# ZHSD-ZYNQ-DDR.net
KiCad netlist of a schematic drawn in Altium Designer
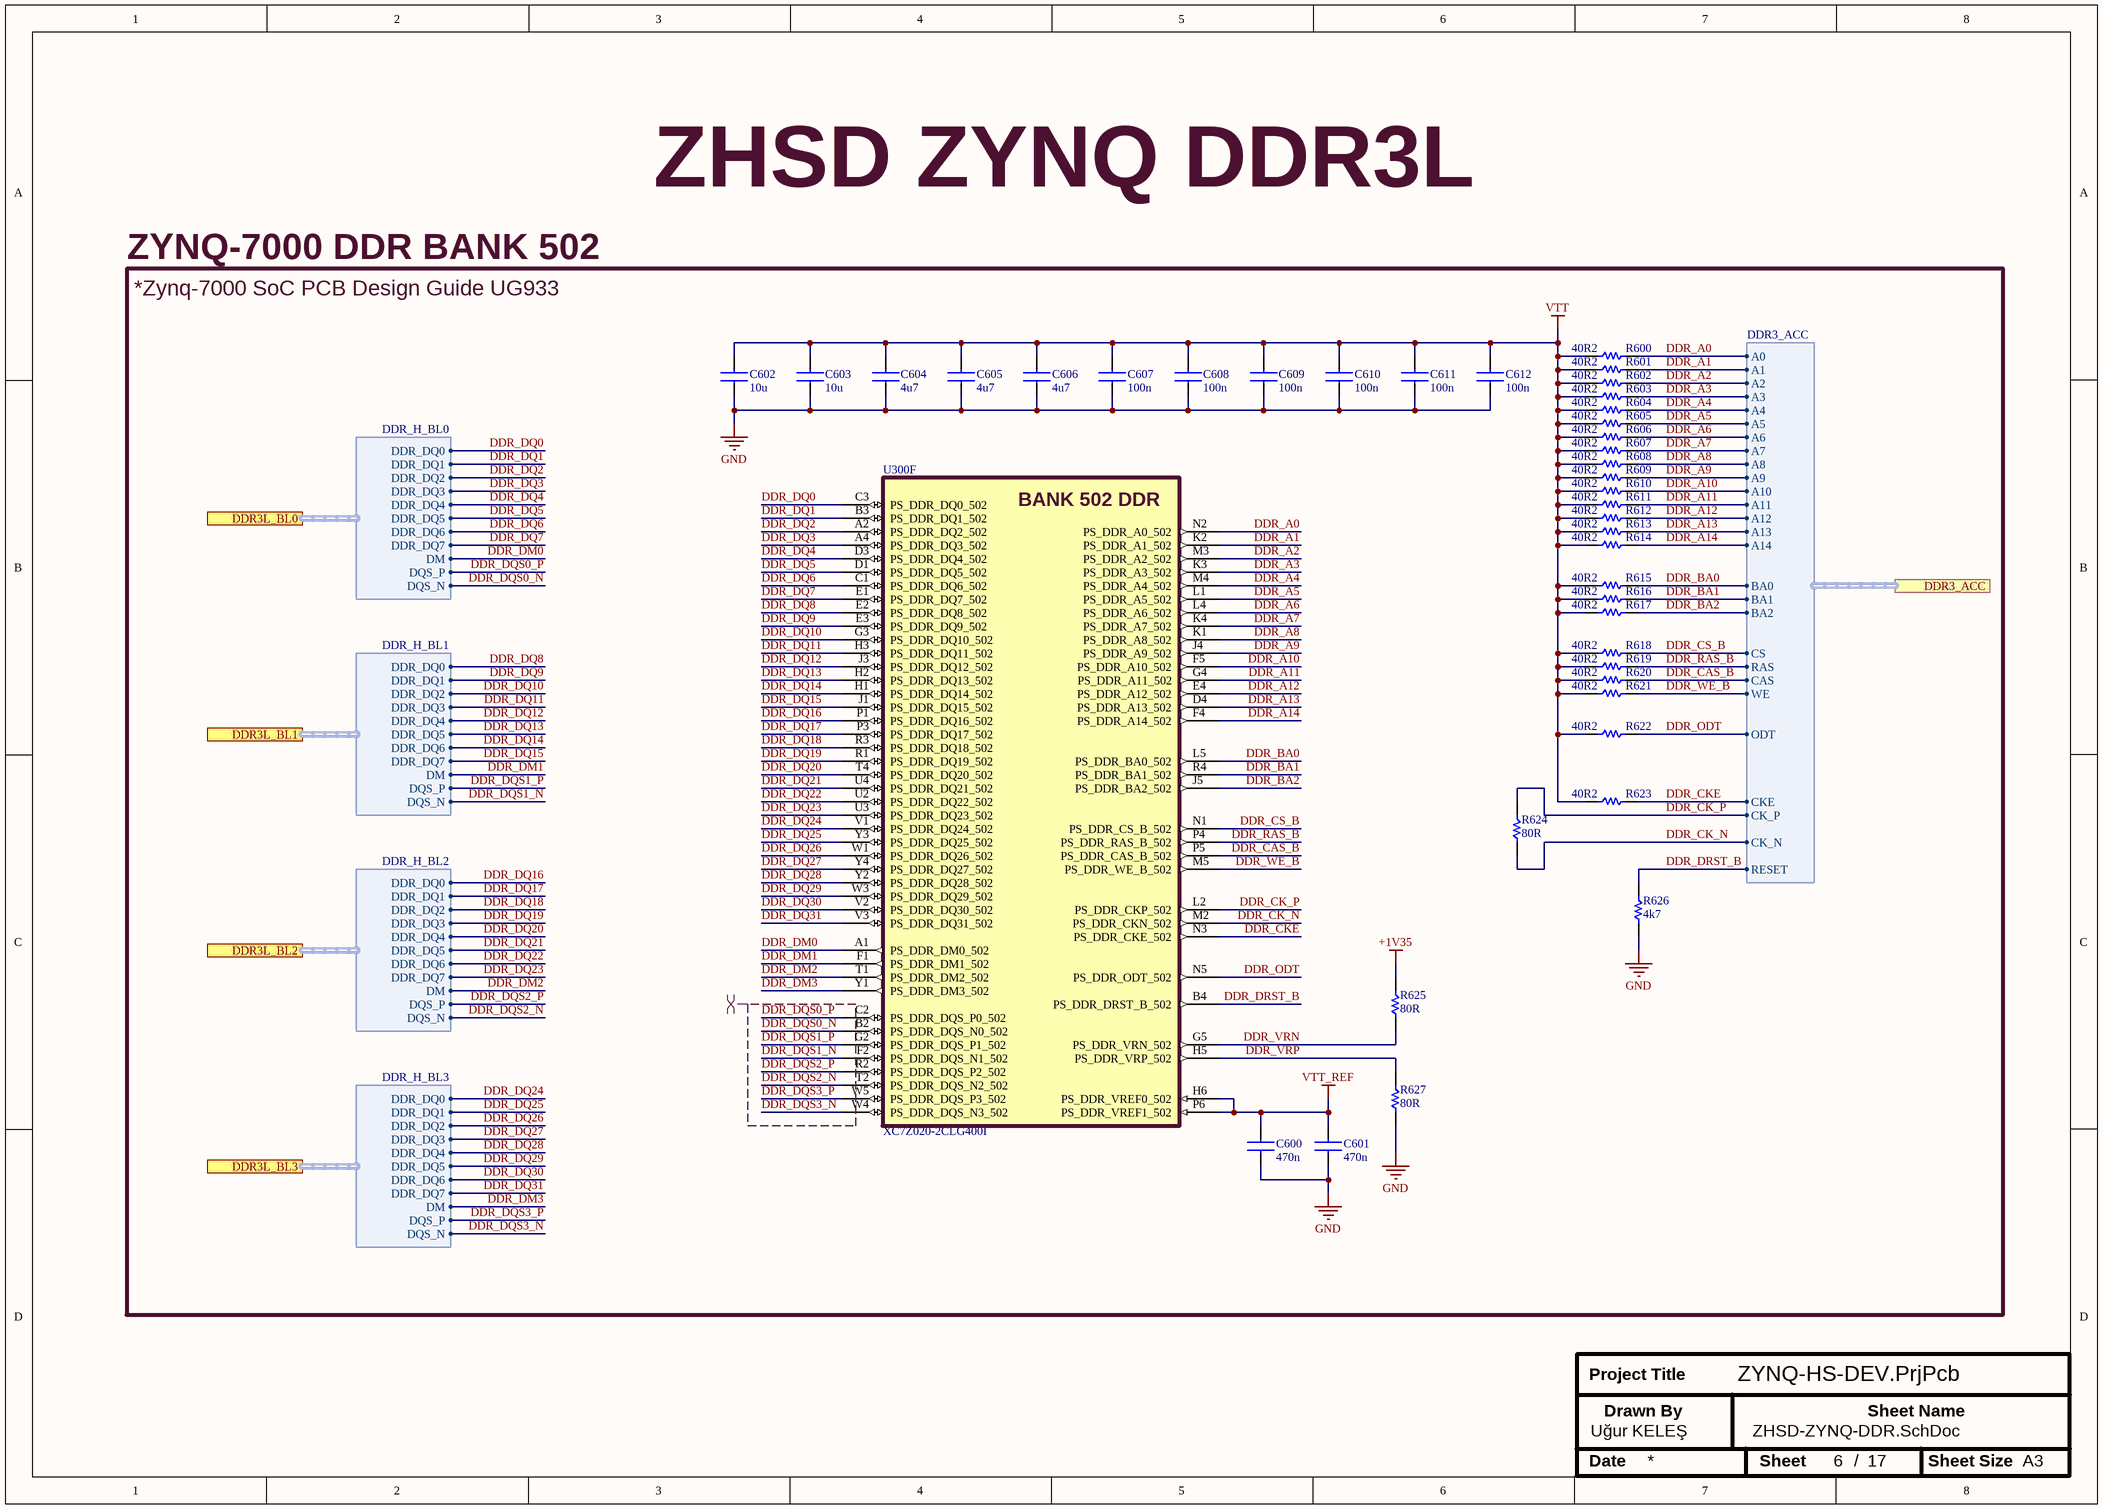
[diagram p0: ZHSD-ZYNQ-DDR.SchDoc]

(export (version "E")
  (design (tool "Eeschema 10.0.6"))
  (components
    (comp (ref "C600")
      (value "470n")
      (footprint "0402CAPC1005X06N")
      (description "CAP CER 0.47UF 6.3V X5R 0402(1005) ±10%")
      (fields (field (name "MANUFACTURER") "Murata Electronics") (field (name "MPN") "GRM155R60J474KE19D"))
      (libsource (lib "UK_Library") (part "GRM155R60J474KE19D"))
    )
    (comp (ref "C601")
      (value "470n")
      (footprint "0402CAPC1005X06N")
      (description "CAP CER 0.47UF 6.3V X5R 0402(1005) ±10%")
      (fields (field (name "MANUFACTURER") "Murata Electronics") (field (name "MPN") "GRM155R60J474KE19D"))
      (libsource (lib "UK_Library") (part "GRM155R60J474KE19D"))
    )
    (comp (ref "C602")
      (value "10u")
      (footprint "0603CAPC1608X09N")
      (description "CAP CER 10UF 10V X7R 0603 (1608) ±20%")
      (fields (field (name "MANUFACTURER") "Murata Electronics") (field (name "MPN") "GRM188Z71A106MA73D"))
      (libsource (lib "UK_Library") (part "GRM188Z71A106MA73D"))
    )
    (comp (ref "C603")
      (value "10u")
      (footprint "0603CAPC1608X09N")
      (description "CAP CER 10UF 10V X7R 0603 (1608) ±20%")
      (fields (field (name "MANUFACTURER") "Murata Electronics") (field (name "MPN") "GRM188Z71A106MA73D"))
      (libsource (lib "UK_Library") (part "GRM188Z71A106MA73D"))
    )
    (comp (ref "C604")
      (value "4u7")
      (footprint "0603CAPC1608X09N")
      (description "CAP CER 4.7UF 10V X5R 0603 (1608) ±10%")
      (fields
        (field (name "MANUFACTURER") "Samsung Electro-Mechanics")
        (field (name "MPN") "CL10A475KP8NNNC")
      )
      (libsource (lib "UK_Library") (part "CL10A475KP8NNNC"))
    )
    (comp (ref "C605")
      (value "4u7")
      (footprint "0603CAPC1608X09N")
      (description "CAP CER 4.7UF 10V X5R 0603 (1608) ±10%")
      (fields
        (field (name "MANUFACTURER") "Samsung Electro-Mechanics")
        (field (name "MPN") "CL10A475KP8NNNC")
      )
      (libsource (lib "UK_Library") (part "CL10A475KP8NNNC"))
    )
    (comp (ref "C606")
      (value "4u7")
      (footprint "0603CAPC1608X09N")
      (description "CAP CER 4.7UF 10V X5R 0603 (1608) ±10%")
      (fields
        (field (name "MANUFACTURER") "Samsung Electro-Mechanics")
        (field (name "MPN") "CL10A475KP8NNNC")
      )
      (libsource (lib "UK_Library") (part "CL10A475KP8NNNC"))
    )
    (comp (ref "C607")
      (value "100n")
      (footprint "0603CAPC1608X09N")
      (description "CAP CER 0.1UF 16V X7R 0402 (1005) ±10%")
      (fields (field (name "MANUFACTURER") "Murata Electronics") (field (name "MPN") "GRM155R71C104KA88J"))
      (libsource (lib "UK_Library") (part "GRM155R71C104KA88J"))
    )
    (comp (ref "C608")
      (value "100n")
      (footprint "0603CAPC1608X09N")
      (description "CAP CER 0.1UF 16V X7R 0402 (1005) ±10%")
      (fields (field (name "MANUFACTURER") "Murata Electronics") (field (name "MPN") "GRM155R71C104KA88J"))
      (libsource (lib "UK_Library") (part "GRM155R71C104KA88J"))
    )
    (comp (ref "C609")
      (value "100n")
      (footprint "0603CAPC1608X09N")
      (description "CAP CER 0.1UF 16V X7R 0402 (1005) ±10%")
      (fields (field (name "MANUFACTURER") "Murata Electronics") (field (name "MPN") "GRM155R71C104KA88J"))
      (libsource (lib "UK_Library") (part "GRM155R71C104KA88J"))
    )
    (comp (ref "C610")
      (value "100n")
      (footprint "0603CAPC1608X09N")
      (description "CAP CER 0.1UF 16V X7R 0402 (1005) ±10%")
      (fields (field (name "MANUFACTURER") "Murata Electronics") (field (name "MPN") "GRM155R71C104KA88J"))
      (libsource (lib "UK_Library") (part "GRM155R71C104KA88J"))
    )
    (comp (ref "C611")
      (value "100n")
      (footprint "0603CAPC1608X09N")
      (description "CAP CER 0.1UF 16V X7R 0402 (1005) ±10%")
      (fields (field (name "MANUFACTURER") "Murata Electronics") (field (name "MPN") "GRM155R71C104KA88J"))
      (libsource (lib "UK_Library") (part "GRM155R71C104KA88J"))
    )
    (comp (ref "C612")
      (value "100n")
      (footprint "0603CAPC1608X09N")
      (description "CAP CER 0.1UF 16V X7R 0402 (1005) ±10%")
      (fields (field (name "MANUFACTURER") "Murata Electronics") (field (name "MPN") "GRM155R71C104KA88J"))
      (libsource (lib "UK_Library") (part "GRM155R71C104KA88J"))
    )
    (comp (ref "R600")
      (value "40R2")
      (footprint "0402RESC1005X04N")
      (description "RES 40.2 OHM 1% 1/16W 0402 (1005)")
      (fields (field (name "MANUFACTURER") "YAGEO") (field (name "MPN") "RC0402FR-0740R2L"))
      (libsource (lib "UK_Library") (part "RC0402FR-0740R2L"))
    )
    (comp (ref "R601")
      (value "40R2")
      (footprint "0402RESC1005X04N")
      (description "RES 40.2 OHM 1% 1/16W 0402 (1005)")
      (fields (field (name "MANUFACTURER") "YAGEO") (field (name "MPN") "RC0402FR-0740R2L"))
      (libsource (lib "UK_Library") (part "RC0402FR-0740R2L"))
    )
    (comp (ref "R602")
      (value "40R2")
      (footprint "0402RESC1005X04N")
      (description "RES 40.2 OHM 1% 1/16W 0402 (1005)")
      (fields (field (name "MANUFACTURER") "YAGEO") (field (name "MPN") "RC0402FR-0740R2L"))
      (libsource (lib "UK_Library") (part "RC0402FR-0740R2L"))
    )
    (comp (ref "R603")
      (value "40R2")
      (footprint "0402RESC1005X04N")
      (description "RES 40.2 OHM 1% 1/16W 0402 (1005)")
      (fields (field (name "MANUFACTURER") "YAGEO") (field (name "MPN") "RC0402FR-0740R2L"))
      (libsource (lib "UK_Library") (part "RC0402FR-0740R2L"))
    )
    (comp (ref "R604")
      (value "40R2")
      (footprint "0402RESC1005X04N")
      (description "RES 40.2 OHM 1% 1/16W 0402 (1005)")
      (fields (field (name "MANUFACTURER") "YAGEO") (field (name "MPN") "RC0402FR-0740R2L"))
      (libsource (lib "UK_Library") (part "RC0402FR-0740R2L"))
    )
    (comp (ref "R605")
      (value "40R2")
      (footprint "0402RESC1005X04N")
      (description "RES 40.2 OHM 1% 1/16W 0402 (1005)")
      (fields (field (name "MANUFACTURER") "YAGEO") (field (name "MPN") "RC0402FR-0740R2L"))
      (libsource (lib "UK_Library") (part "RC0402FR-0740R2L"))
    )
    (comp (ref "R606")
      (value "40R2")
      (footprint "0402RESC1005X04N")
      (description "RES 40.2 OHM 1% 1/16W 0402 (1005)")
      (fields (field (name "MANUFACTURER") "YAGEO") (field (name "MPN") "RC0402FR-0740R2L"))
      (libsource (lib "UK_Library") (part "RC0402FR-0740R2L"))
    )
    (comp (ref "R607")
      (value "40R2")
      (footprint "0402RESC1005X04N")
      (description "RES 40.2 OHM 1% 1/16W 0402 (1005)")
      (fields (field (name "MANUFACTURER") "YAGEO") (field (name "MPN") "RC0402FR-0740R2L"))
      (libsource (lib "UK_Library") (part "RC0402FR-0740R2L"))
    )
    (comp (ref "R608")
      (value "40R2")
      (footprint "0402RESC1005X04N")
      (description "RES 40.2 OHM 1% 1/16W 0402 (1005)")
      (fields (field (name "MANUFACTURER") "YAGEO") (field (name "MPN") "RC0402FR-0740R2L"))
      (libsource (lib "UK_Library") (part "RC0402FR-0740R2L"))
    )
    (comp (ref "R609")
      (value "40R2")
      (footprint "0402RESC1005X04N")
      (description "RES 40.2 OHM 1% 1/16W 0402 (1005)")
      (fields (field (name "MANUFACTURER") "YAGEO") (field (name "MPN") "RC0402FR-0740R2L"))
      (libsource (lib "UK_Library") (part "RC0402FR-0740R2L"))
    )
    (comp (ref "R610")
      (value "40R2")
      (footprint "0402RESC1005X04N")
      (description "RES 40.2 OHM 1% 1/16W 0402 (1005)")
      (fields (field (name "MANUFACTURER") "YAGEO") (field (name "MPN") "RC0402FR-0740R2L"))
      (libsource (lib "UK_Library") (part "RC0402FR-0740R2L"))
    )
    (comp (ref "R611")
      (value "40R2")
      (footprint "0402RESC1005X04N")
      (description "RES 40.2 OHM 1% 1/16W 0402 (1005)")
      (fields (field (name "MANUFACTURER") "YAGEO") (field (name "MPN") "RC0402FR-0740R2L"))
      (libsource (lib "UK_Library") (part "RC0402FR-0740R2L"))
    )
    (comp (ref "R612")
      (value "40R2")
      (footprint "0402RESC1005X04N")
      (description "RES 40.2 OHM 1% 1/16W 0402 (1005)")
      (fields (field (name "MANUFACTURER") "YAGEO") (field (name "MPN") "RC0402FR-0740R2L"))
      (libsource (lib "UK_Library") (part "RC0402FR-0740R2L"))
    )
    (comp (ref "R613")
      (value "40R2")
      (footprint "0402RESC1005X04N")
      (description "RES 40.2 OHM 1% 1/16W 0402 (1005)")
      (fields (field (name "MANUFACTURER") "YAGEO") (field (name "MPN") "RC0402FR-0740R2L"))
      (libsource (lib "UK_Library") (part "RC0402FR-0740R2L"))
    )
    (comp (ref "R614")
      (value "40R2")
      (footprint "0402RESC1005X04N")
      (description "RES 40.2 OHM 1% 1/16W 0402 (1005)")
      (fields (field (name "MANUFACTURER") "YAGEO") (field (name "MPN") "RC0402FR-0740R2L"))
      (libsource (lib "UK_Library") (part "RC0402FR-0740R2L"))
    )
    (comp (ref "R615")
      (value "40R2")
      (footprint "0402RESC1005X04N")
      (description "RES 40.2 OHM 1% 1/16W 0402 (1005)")
      (fields (field (name "MANUFACTURER") "YAGEO") (field (name "MPN") "RC0402FR-0740R2L"))
      (libsource (lib "UK_Library") (part "RC0402FR-0740R2L"))
    )
    (comp (ref "R616")
      (value "40R2")
      (footprint "0402RESC1005X04N")
      (description "RES 40.2 OHM 1% 1/16W 0402 (1005)")
      (fields (field (name "MANUFACTURER") "YAGEO") (field (name "MPN") "RC0402FR-0740R2L"))
      (libsource (lib "UK_Library") (part "RC0402FR-0740R2L"))
    )
    (comp (ref "R617")
      (value "40R2")
      (footprint "0402RESC1005X04N")
      (description "RES 40.2 OHM 1% 1/16W 0402 (1005)")
      (fields (field (name "MANUFACTURER") "YAGEO") (field (name "MPN") "RC0402FR-0740R2L"))
      (libsource (lib "UK_Library") (part "RC0402FR-0740R2L"))
    )
    (comp (ref "R618")
      (value "40R2")
      (footprint "0402RESC1005X04N")
      (description "RES 40.2 OHM 1% 1/16W 0402 (1005)")
      (fields (field (name "MANUFACTURER") "YAGEO") (field (name "MPN") "RC0402FR-0740R2L"))
      (libsource (lib "UK_Library") (part "RC0402FR-0740R2L"))
    )
    (comp (ref "R619")
      (value "40R2")
      (footprint "0402RESC1005X04N")
      (description "RES 40.2 OHM 1% 1/16W 0402 (1005)")
      (fields (field (name "MANUFACTURER") "YAGEO") (field (name "MPN") "RC0402FR-0740R2L"))
      (libsource (lib "UK_Library") (part "RC0402FR-0740R2L"))
    )
    (comp (ref "R620")
      (value "40R2")
      (footprint "0402RESC1005X04N")
      (description "RES 40.2 OHM 1% 1/16W 0402 (1005)")
      (fields (field (name "MANUFACTURER") "YAGEO") (field (name "MPN") "RC0402FR-0740R2L"))
      (libsource (lib "UK_Library") (part "RC0402FR-0740R2L"))
    )
    (comp (ref "R621")
      (value "40R2")
      (footprint "0402RESC1005X04N")
      (description "RES 40.2 OHM 1% 1/16W 0402 (1005)")
      (fields (field (name "MANUFACTURER") "YAGEO") (field (name "MPN") "RC0402FR-0740R2L"))
      (libsource (lib "UK_Library") (part "RC0402FR-0740R2L"))
    )
    (comp (ref "R622")
      (value "40R2")
      (footprint "0402RESC1005X04N")
      (description "RES 40.2 OHM 1% 1/16W 0402 (1005)")
      (fields (field (name "MANUFACTURER") "YAGEO") (field (name "MPN") "RC0402FR-0740R2L"))
      (libsource (lib "UK_Library") (part "RC0402FR-0740R2L"))
    )
    (comp (ref "R623")
      (value "40R2")
      (footprint "0402RESC1005X04N")
      (description "RES 40.2 OHM 1% 1/16W 0402 (1005)")
      (fields (field (name "MANUFACTURER") "YAGEO") (field (name "MPN") "RC0402FR-0740R2L"))
      (libsource (lib "UK_Library") (part "RC0402FR-0740R2L"))
    )
    (comp (ref "R624")
      (value "80R")
      (footprint "0402RESC1005X04N")
      (description "RES 80 OHM 1% 1/16W 0402 (1005)")
      (fields (field (name "MANUFACTURER") "YAGEO") (field (name "MPN") "RT0402FRE0780RL"))
      (libsource (lib "UK_Library") (part "RT0402FRE0780RL"))
    )
    (comp (ref "R625")
      (value "80R")
      (footprint "0402RESC1005X04N")
      (description "RES 80 OHM 1% 1/16W 0402 (1005)")
      (fields (field (name "MANUFACTURER") "YAGEO") (field (name "MPN") "RT0402FRE0780RL"))
      (libsource (lib "UK_Library") (part "RT0402FRE0780RL"))
    )
    (comp (ref "R626")
      (value "4k7")
      (footprint "0402RESC1005X04N")
      (description "RES 4.7K OHM 5% 1/16W 0402 (1005)")
      (fields (field (name "MANUFACTURER") "YAGEO") (field (name "MPN") "RT0402FRE0780RL"))
      (libsource (lib "UK_Library") (part "RC0402JR-074K7L"))
    )
    (comp (ref "R627")
      (value "80R")
      (footprint "0402RESC1005X04N")
      (description "RES 80 OHM 1% 1/16W 0402 (1005)")
      (fields (field (name "MANUFACTURER") "YAGEO") (field (name "MPN") "RT0402FRE0780RL"))
      (libsource (lib "UK_Library") (part "RT0402FRE0780RL"))
    )
    (comp (ref "U300")
      (value "XC7Z020-2CLG400I")
      (footprint "BGA400C80P20X20_1700X1700X147")
      (fields (field (name "MANUFACTURER") "AMD/XILINX"))
      (libsource (lib "UK_Library") (part "XC7Z020-2CLG400I"))
    )
  )
  (nets
    (net (code "6") (name "+1V35") (class "Default")
      (node (ref "R625") (pin "2") (pinfunction "2_2") (pintype "passive"))
    )
    (net (code "7") (name "/DDR_A0") (class "Default")
      (node (ref "R600") (pin "2") (pinfunction "2_2") (pintype "passive"))
      (node (ref "U300") (pin "N2") (pinfunction "PS_DDR_A0_502_N2") (pintype "output"))
    )
    (net (code "8") (name "/DDR_A1") (class "Default")
      (node (ref "R601") (pin "2") (pinfunction "2_2") (pintype "passive"))
      (node (ref "U300") (pin "K2") (pinfunction "PS_DDR_A1_502_K2") (pintype "output"))
    )
    (net (code "9") (name "/DDR_A2") (class "Default")
      (node (ref "R602") (pin "2") (pinfunction "2_2") (pintype "passive"))
      (node (ref "U300") (pin "M3") (pinfunction "PS_DDR_A2_502_M3") (pintype "output"))
    )
    (net (code "10") (name "/DDR_A3") (class "Default")
      (node (ref "R603") (pin "2") (pinfunction "2_2") (pintype "passive"))
      (node (ref "U300") (pin "K3") (pinfunction "PS_DDR_A3_502_K3") (pintype "output"))
    )
    (net (code "11") (name "/DDR_A4") (class "Default")
      (node (ref "R604") (pin "2") (pinfunction "2_2") (pintype "passive"))
      (node (ref "U300") (pin "M4") (pinfunction "PS_DDR_A4_502_M4") (pintype "output"))
    )
    (net (code "12") (name "/DDR_A5") (class "Default")
      (node (ref "R605") (pin "2") (pinfunction "2_2") (pintype "passive"))
      (node (ref "U300") (pin "L1") (pinfunction "PS_DDR_A5_502_L1") (pintype "output"))
    )
    (net (code "13") (name "/DDR_A6") (class "Default")
      (node (ref "R606") (pin "2") (pinfunction "2_2") (pintype "passive"))
      (node (ref "U300") (pin "L4") (pinfunction "PS_DDR_A6_502_L4") (pintype "output"))
    )
    (net (code "14") (name "/DDR_A7") (class "Default")
      (node (ref "R607") (pin "2") (pinfunction "2_2") (pintype "passive"))
      (node (ref "U300") (pin "K4") (pinfunction "PS_DDR_A7_502_K4") (pintype "output"))
    )
    (net (code "15") (name "/DDR_A8") (class "Default")
      (node (ref "R608") (pin "2") (pinfunction "2_2") (pintype "passive"))
      (node (ref "U300") (pin "K1") (pinfunction "PS_DDR_A8_502_K1") (pintype "output"))
    )
    (net (code "16") (name "/DDR_A9") (class "Default")
      (node (ref "R609") (pin "2") (pinfunction "2_2") (pintype "passive"))
      (node (ref "U300") (pin "J4") (pinfunction "PS_DDR_A9_502_J4") (pintype "output"))
    )
    (net (code "17") (name "/DDR_A10") (class "Default")
      (node (ref "R610") (pin "2") (pinfunction "2_2") (pintype "passive"))
      (node (ref "U300") (pin "F5") (pinfunction "PS_DDR_A10_502_F5") (pintype "output"))
    )
    (net (code "18") (name "/DDR_A11") (class "Default")
      (node (ref "R611") (pin "2") (pinfunction "2_2") (pintype "passive"))
      (node (ref "U300") (pin "G4") (pinfunction "PS_DDR_A11_502_G4") (pintype "output"))
    )
    (net (code "19") (name "/DDR_A12") (class "Default")
      (node (ref "R612") (pin "2") (pinfunction "2_2") (pintype "passive"))
      (node (ref "U300") (pin "E4") (pinfunction "PS_DDR_A12_502_E4") (pintype "output"))
    )
    (net (code "20") (name "/DDR_A13") (class "Default")
      (node (ref "R613") (pin "2") (pinfunction "2_2") (pintype "passive"))
      (node (ref "U300") (pin "D4") (pinfunction "PS_DDR_A13_502_D4") (pintype "output"))
    )
    (net (code "21") (name "/DDR_A14") (class "Default")
      (node (ref "R614") (pin "2") (pinfunction "2_2") (pintype "passive"))
      (node (ref "U300") (pin "F4") (pinfunction "PS_DDR_A14_502_F4") (pintype "output"))
    )
    (net (code "22") (name "/DDR_BA0") (class "Default")
      (node (ref "R615") (pin "2") (pinfunction "2_2") (pintype "passive"))
      (node (ref "U300") (pin "L5") (pinfunction "PS_DDR_BA0_502_L5") (pintype "output"))
    )
    (net (code "23") (name "/DDR_BA1") (class "Default")
      (node (ref "R616") (pin "2") (pinfunction "2_2") (pintype "passive"))
      (node (ref "U300") (pin "R4") (pinfunction "PS_DDR_BA1_502_R4") (pintype "output"))
    )
    (net (code "24") (name "/DDR_BA2") (class "Default")
      (node (ref "R617") (pin "2") (pinfunction "2_2") (pintype "passive"))
      (node (ref "U300") (pin "J5") (pinfunction "PS_DDR_BA2_502_J5") (pintype "output"))
    )
    (net (code "25") (name "/DDR_CAS_B") (class "Default")
      (node (ref "R620") (pin "2") (pinfunction "2_2") (pintype "passive"))
      (node (ref "U300") (pin "P5") (pinfunction "PS_DDR_CAS_B_502_P5") (pintype "output"))
    )
    (net (code "26") (name "/DDR_CKE") (class "Default")
      (node (ref "R623") (pin "2") (pinfunction "2_2") (pintype "passive"))
      (node (ref "U300") (pin "N3") (pinfunction "PS_DDR_CKE_502_N3") (pintype "output"))
    )
    (net (code "27") (name "/DDR_CK_N") (class "Default")
      (node (ref "R624") (pin "1") (pinfunction "1_1") (pintype "passive"))
      (node (ref "U300") (pin "M2") (pinfunction "PS_DDR_CKN_502_M2") (pintype "output"))
    )
    (net (code "28") (name "/DDR_CK_P") (class "Default")
      (node (ref "R624") (pin "2") (pinfunction "2_2") (pintype "passive"))
      (node (ref "U300") (pin "L2") (pinfunction "PS_DDR_CKP_502_L2") (pintype "output"))
    )
    (net (code "29") (name "/DDR_CS_B") (class "Default")
      (node (ref "R618") (pin "2") (pinfunction "2_2") (pintype "passive"))
      (node (ref "U300") (pin "N1") (pinfunction "PS_DDR_CS_B_502_N1") (pintype "output"))
    )
    (net (code "30") (name "/DDR_DM0") (class "Default")
      (node (ref "U300") (pin "A1") (pinfunction "PS_DDR_DM0_502_A1") (pintype "output"))
    )
    (net (code "31") (name "/DDR_DM1") (class "Default")
      (node (ref "U300") (pin "F1") (pinfunction "PS_DDR_DM1_502_F1") (pintype "output"))
    )
    (net (code "32") (name "/DDR_DM2") (class "Default")
      (node (ref "U300") (pin "T1") (pinfunction "PS_DDR_DM2_502_T1") (pintype "output"))
    )
    (net (code "33") (name "/DDR_DM3") (class "Default")
      (node (ref "U300") (pin "Y1") (pinfunction "PS_DDR_DM3_502_Y1") (pintype "output"))
    )
    (net (code "34") (name "/DDR_DQ0") (class "Default")
      (node (ref "U300") (pin "C3") (pinfunction "PS_DDR_DQ0_502_C3") (pintype "bidirectional"))
    )
    (net (code "35") (name "/DDR_DQ1") (class "Default")
      (node (ref "U300") (pin "B3") (pinfunction "PS_DDR_DQ1_502_B3") (pintype "bidirectional"))
    )
    (net (code "36") (name "/DDR_DQ2") (class "Default")
      (node (ref "U300") (pin "A2") (pinfunction "PS_DDR_DQ2_502_A2") (pintype "bidirectional"))
    )
    (net (code "37") (name "/DDR_DQ3") (class "Default")
      (node (ref "U300") (pin "A4") (pinfunction "PS_DDR_DQ3_502_A4") (pintype "bidirectional"))
    )
    (net (code "38") (name "/DDR_DQ4") (class "Default")
      (node (ref "U300") (pin "D3") (pinfunction "PS_DDR_DQ4_502_D3") (pintype "bidirectional"))
    )
    (net (code "39") (name "/DDR_DQ5") (class "Default")
      (node (ref "U300") (pin "D1") (pinfunction "PS_DDR_DQ5_502_D1") (pintype "bidirectional"))
    )
    (net (code "40") (name "/DDR_DQ6") (class "Default")
      (node (ref "U300") (pin "C1") (pinfunction "PS_DDR_DQ6_502_C1") (pintype "bidirectional"))
    )
    (net (code "41") (name "/DDR_DQ7") (class "Default")
      (node (ref "U300") (pin "E1") (pinfunction "PS_DDR_DQ7_502_E1") (pintype "bidirectional"))
    )
    (net (code "42") (name "/DDR_DQ8") (class "Default")
      (node (ref "U300") (pin "E2") (pinfunction "PS_DDR_DQ8_502_E2") (pintype "bidirectional"))
    )
    (net (code "43") (name "/DDR_DQ9") (class "Default")
      (node (ref "U300") (pin "E3") (pinfunction "PS_DDR_DQ9_502_E3") (pintype "bidirectional"))
    )
    (net (code "44") (name "/DDR_DQ10") (class "Default")
      (node (ref "U300") (pin "G3") (pinfunction "PS_DDR_DQ10_502_G3") (pintype "bidirectional"))
    )
    (net (code "45") (name "/DDR_DQ11") (class "Default")
      (node (ref "U300") (pin "H3") (pinfunction "PS_DDR_DQ11_502_H3") (pintype "bidirectional"))
    )
    (net (code "46") (name "/DDR_DQ12") (class "Default")
      (node (ref "U300") (pin "J3") (pinfunction "PS_DDR_DQ12_502_J3") (pintype "bidirectional"))
    )
    (net (code "47") (name "/DDR_DQ13") (class "Default")
      (node (ref "U300") (pin "H2") (pinfunction "PS_DDR_DQ13_502_H2") (pintype "bidirectional"))
    )
    (net (code "48") (name "/DDR_DQ14") (class "Default")
      (node (ref "U300") (pin "H1") (pinfunction "PS_DDR_DQ14_502_H1") (pintype "bidirectional"))
    )
    (net (code "49") (name "/DDR_DQ15") (class "Default")
      (node (ref "U300") (pin "J1") (pinfunction "PS_DDR_DQ15_502_J1") (pintype "bidirectional"))
    )
    (net (code "50") (name "/DDR_DQ16") (class "Default")
      (node (ref "U300") (pin "P1") (pinfunction "PS_DDR_DQ16_502_P1") (pintype "bidirectional"))
    )
    (net (code "51") (name "/DDR_DQ17") (class "Default")
      (node (ref "U300") (pin "P3") (pinfunction "PS_DDR_DQ17_502_P3") (pintype "bidirectional"))
    )
    (net (code "52") (name "/DDR_DQ18") (class "Default")
      (node (ref "U300") (pin "R3") (pinfunction "PS_DDR_DQ18_502_R3") (pintype "bidirectional"))
    )
    (net (code "53") (name "/DDR_DQ19") (class "Default")
      (node (ref "U300") (pin "R1") (pinfunction "PS_DDR_DQ19_502_R1") (pintype "bidirectional"))
    )
    (net (code "54") (name "/DDR_DQ20") (class "Default")
      (node (ref "U300") (pin "T4") (pinfunction "PS_DDR_DQ20_502_T4") (pintype "bidirectional"))
    )
    (net (code "55") (name "/DDR_DQ21") (class "Default")
      (node (ref "U300") (pin "U4") (pinfunction "PS_DDR_DQ21_502_U4") (pintype "bidirectional"))
    )
    (net (code "56") (name "/DDR_DQ22") (class "Default")
      (node (ref "U300") (pin "U2") (pinfunction "PS_DDR_DQ22_502_U2") (pintype "bidirectional"))
    )
    (net (code "57") (name "/DDR_DQ23") (class "Default")
      (node (ref "U300") (pin "U3") (pinfunction "PS_DDR_DQ23_502_U3") (pintype "bidirectional"))
    )
    (net (code "58") (name "/DDR_DQ24") (class "Default")
      (node (ref "U300") (pin "V1") (pinfunction "PS_DDR_DQ24_502_V1") (pintype "bidirectional"))
    )
    (net (code "59") (name "/DDR_DQ25") (class "Default")
      (node (ref "U300") (pin "Y3") (pinfunction "PS_DDR_DQ25_502_Y3") (pintype "bidirectional"))
    )
    (net (code "60") (name "/DDR_DQ26") (class "Default")
      (node (ref "U300") (pin "W1") (pinfunction "PS_DDR_DQ26_502_W1") (pintype "bidirectional"))
    )
    (net (code "61") (name "/DDR_DQ27") (class "Default")
      (node (ref "U300") (pin "Y4") (pinfunction "PS_DDR_DQ27_502_Y4") (pintype "bidirectional"))
    )
    (net (code "62") (name "/DDR_DQ28") (class "Default")
      (node (ref "U300") (pin "Y2") (pinfunction "PS_DDR_DQ28_502_Y2") (pintype "bidirectional"))
    )
    (net (code "63") (name "/DDR_DQ29") (class "Default")
      (node (ref "U300") (pin "W3") (pinfunction "PS_DDR_DQ29_502_W3") (pintype "bidirectional"))
    )
    (net (code "64") (name "/DDR_DQ30") (class "Default")
      (node (ref "U300") (pin "V2") (pinfunction "PS_DDR_DQ30_502_V2") (pintype "bidirectional"))
    )
    (net (code "65") (name "/DDR_DQ31") (class "Default")
      (node (ref "U300") (pin "V3") (pinfunction "PS_DDR_DQ31_502_V3") (pintype "bidirectional"))
    )
    (net (code "66") (name "/DDR_DQS0_N") (class "Default")
      (node (ref "U300") (pin "B2") (pinfunction "PS_DDR_DQS_N0_502_B2") (pintype "bidirectional"))
    )
    (net (code "67") (name "/DDR_DQS0_P") (class "Default")
      (node (ref "U300") (pin "C2") (pinfunction "PS_DDR_DQS_P0_502_C2") (pintype "bidirectional"))
    )
    (net (code "68") (name "/DDR_DQS1_N") (class "Default")
      (node (ref "U300") (pin "F2") (pinfunction "PS_DDR_DQS_N1_502_F2") (pintype "bidirectional"))
    )
    (net (code "69") (name "/DDR_DQS1_P") (class "Default")
      (node (ref "U300") (pin "G2") (pinfunction "PS_DDR_DQS_P1_502_G2") (pintype "bidirectional"))
    )
    (net (code "70") (name "/DDR_DQS2_N") (class "Default")
      (node (ref "U300") (pin "T2") (pinfunction "PS_DDR_DQS_N2_502_T2") (pintype "bidirectional"))
    )
    (net (code "71") (name "/DDR_DQS2_P") (class "Default")
      (node (ref "U300") (pin "R2") (pinfunction "PS_DDR_DQS_P2_502_R2") (pintype "bidirectional"))
    )
    (net (code "72") (name "/DDR_DQS3_N") (class "Default")
      (node (ref "U300") (pin "W4") (pinfunction "PS_DDR_DQS_N3_502_W4") (pintype "bidirectional"))
    )
    (net (code "73") (name "/DDR_DQS3_P") (class "Default")
      (node (ref "U300") (pin "W5") (pinfunction "PS_DDR_DQS_P3_502_W5") (pintype "bidirectional"))
    )
    (net (code "74") (name "/DDR_DRST_B") (class "Default")
      (node (ref "R626") (pin "2") (pinfunction "2_2") (pintype "passive"))
      (node (ref "U300") (pin "B4") (pinfunction "PS_DDR_DRST_B_502_B4") (pintype "output"))
    )
    (net (code "75") (name "/DDR_ODT") (class "Default")
      (node (ref "R622") (pin "2") (pinfunction "2_2") (pintype "passive"))
      (node (ref "U300") (pin "N5") (pinfunction "PS_DDR_ODT_502_N5") (pintype "output"))
    )
    (net (code "76") (name "/DDR_RAS_B") (class "Default")
      (node (ref "R619") (pin "2") (pinfunction "2_2") (pintype "passive"))
      (node (ref "U300") (pin "P4") (pinfunction "PS_DDR_RAS_B_502_P4") (pintype "output"))
    )
    (net (code "77") (name "/DDR_VRN") (class "Default")
      (node (ref "R625") (pin "1") (pinfunction "1_1") (pintype "passive"))
      (node (ref "U300") (pin "G5") (pinfunction "PS_DDR_VRN_502_G5") (pintype "output"))
    )
    (net (code "78") (name "/DDR_VRP") (class "Default")
      (node (ref "R627") (pin "2") (pinfunction "2_2") (pintype "passive"))
      (node (ref "U300") (pin "H5") (pinfunction "PS_DDR_VRP_502_H5") (pintype "output"))
    )
    (net (code "79") (name "/DDR_WE_B") (class "Default")
      (node (ref "R621") (pin "2") (pinfunction "2_2") (pintype "passive"))
      (node (ref "U300") (pin "M5") (pinfunction "PS_DDR_WE_B_502_M5") (pintype "output"))
    )
    (net (code "85") (name "GND") (class "Default")
      (node (ref "C600") (pin "1") (pinfunction "1_1") (pintype "passive"))
      (node (ref "C601") (pin "1") (pinfunction "1_1") (pintype "passive"))
      (node (ref "C602") (pin "1") (pinfunction "1_1") (pintype "passive"))
      (node (ref "C603") (pin "1") (pinfunction "1_1") (pintype "passive"))
      (node (ref "C604") (pin "1") (pinfunction "1_1") (pintype "passive"))
      (node (ref "C605") (pin "1") (pinfunction "1_1") (pintype "passive"))
      (node (ref "C606") (pin "1") (pinfunction "1_1") (pintype "passive"))
      (node (ref "C607") (pin "1") (pinfunction "1_1") (pintype "passive"))
      (node (ref "C608") (pin "1") (pinfunction "1_1") (pintype "passive"))
      (node (ref "C609") (pin "1") (pinfunction "1_1") (pintype "passive"))
      (node (ref "C610") (pin "1") (pinfunction "1_1") (pintype "passive"))
      (node (ref "C611") (pin "1") (pinfunction "1_1") (pintype "passive"))
      (node (ref "C612") (pin "1") (pinfunction "1_1") (pintype "passive"))
      (node (ref "R626") (pin "1") (pinfunction "1_1") (pintype "passive"))
      (node (ref "R627") (pin "1") (pinfunction "1_1") (pintype "passive"))
    )
    (net (code "86") (name "VTT") (class "Default")
      (node (ref "C602") (pin "2") (pinfunction "2_2") (pintype "passive"))
      (node (ref "C603") (pin "2") (pinfunction "2_2") (pintype "passive"))
      (node (ref "C604") (pin "2") (pinfunction "2_2") (pintype "passive"))
      (node (ref "C605") (pin "2") (pinfunction "2_2") (pintype "passive"))
      (node (ref "C606") (pin "2") (pinfunction "2_2") (pintype "passive"))
      (node (ref "C607") (pin "2") (pinfunction "2_2") (pintype "passive"))
      (node (ref "C608") (pin "2") (pinfunction "2_2") (pintype "passive"))
      (node (ref "C609") (pin "2") (pinfunction "2_2") (pintype "passive"))
      (node (ref "C610") (pin "2") (pinfunction "2_2") (pintype "passive"))
      (node (ref "C611") (pin "2") (pinfunction "2_2") (pintype "passive"))
      (node (ref "C612") (pin "2") (pinfunction "2_2") (pintype "passive"))
      (node (ref "R600") (pin "1") (pinfunction "1_1") (pintype "passive"))
      (node (ref "R601") (pin "1") (pinfunction "1_1") (pintype "passive"))
      (node (ref "R602") (pin "1") (pinfunction "1_1") (pintype "passive"))
      (node (ref "R603") (pin "1") (pinfunction "1_1") (pintype "passive"))
      (node (ref "R604") (pin "1") (pinfunction "1_1") (pintype "passive"))
      (node (ref "R605") (pin "1") (pinfunction "1_1") (pintype "passive"))
      (node (ref "R606") (pin "1") (pinfunction "1_1") (pintype "passive"))
      (node (ref "R607") (pin "1") (pinfunction "1_1") (pintype "passive"))
      (node (ref "R608") (pin "1") (pinfunction "1_1") (pintype "passive"))
      (node (ref "R609") (pin "1") (pinfunction "1_1") (pintype "passive"))
      (node (ref "R610") (pin "1") (pinfunction "1_1") (pintype "passive"))
      (node (ref "R611") (pin "1") (pinfunction "1_1") (pintype "passive"))
      (node (ref "R612") (pin "1") (pinfunction "1_1") (pintype "passive"))
      (node (ref "R613") (pin "1") (pinfunction "1_1") (pintype "passive"))
      (node (ref "R614") (pin "1") (pinfunction "1_1") (pintype "passive"))
      (node (ref "R615") (pin "1") (pinfunction "1_1") (pintype "passive"))
      (node (ref "R616") (pin "1") (pinfunction "1_1") (pintype "passive"))
      (node (ref "R617") (pin "1") (pinfunction "1_1") (pintype "passive"))
      (node (ref "R618") (pin "1") (pinfunction "1_1") (pintype "passive"))
      (node (ref "R619") (pin "1") (pinfunction "1_1") (pintype "passive"))
      (node (ref "R620") (pin "1") (pinfunction "1_1") (pintype "passive"))
      (node (ref "R621") (pin "1") (pinfunction "1_1") (pintype "passive"))
      (node (ref "R622") (pin "1") (pinfunction "1_1") (pintype "passive"))
      (node (ref "R623") (pin "1") (pinfunction "1_1") (pintype "passive"))
    )
    (net (code "87") (name "VTT_REF") (class "Default")
      (node (ref "C600") (pin "2") (pinfunction "2_2") (pintype "passive"))
      (node (ref "C601") (pin "2") (pinfunction "2_2") (pintype "passive"))
      (node (ref "U300") (pin "H6") (pinfunction "PS_DDR_VREF0_502_H6") (pintype "input"))
      (node (ref "U300") (pin "P6") (pinfunction "PS_DDR_VREF1_502_P6") (pintype "input"))
    )
  )
)
